# Hall_Effect_Arduino.net
KiCad netlist of a schematic drawn in EAGLE
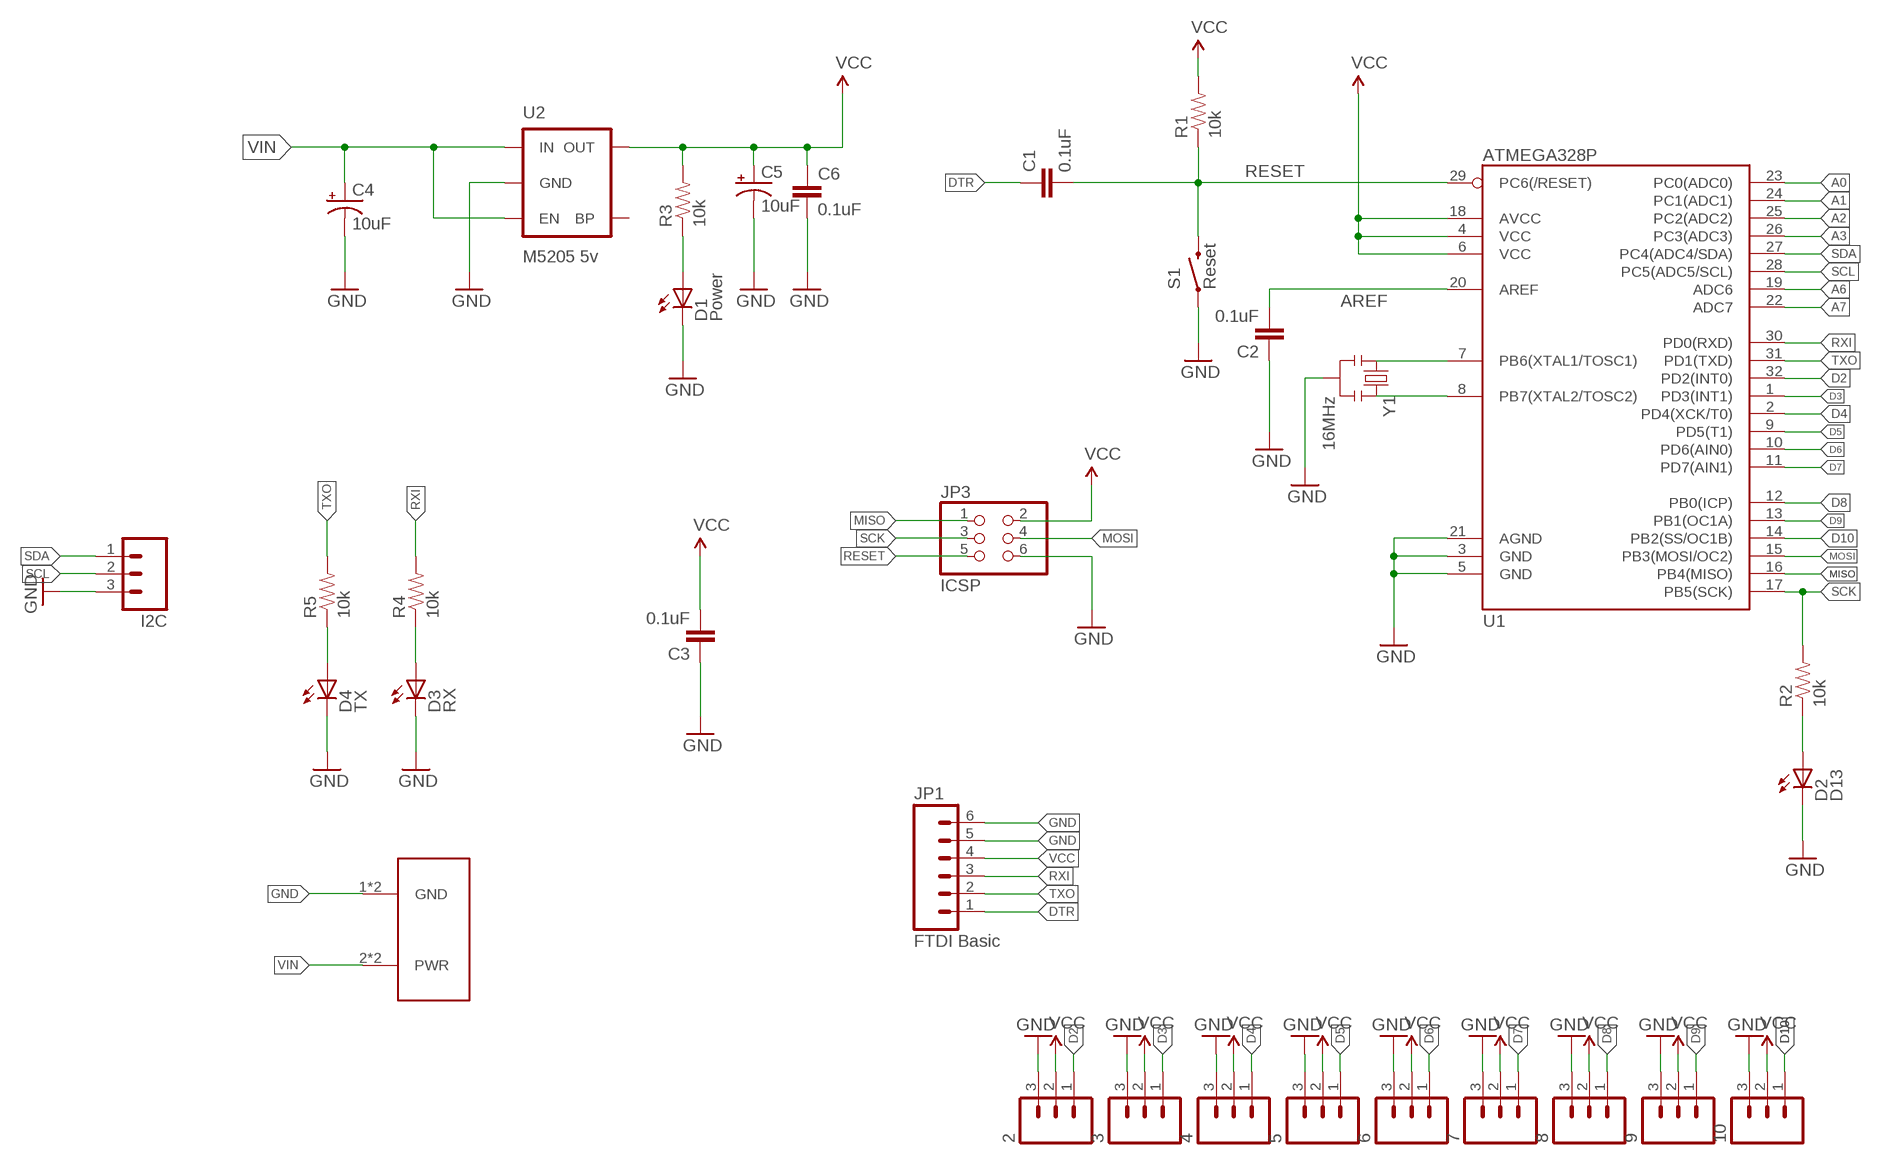
[diagram p0: schematic, sheet 1]

(export (version "E")
  (design (tool "Eeschema 10.0.6"))
  (components
    (comp (ref "2")
      (value "M03PTH")
      (footprint "eagle-import:1X03")
      (libsource (lib "eagle-import") (part "M03PTH"))
    )
    (comp (ref "3")
      (value "M03PTH")
      (footprint "eagle-import:1X03")
      (libsource (lib "eagle-import") (part "M03PTH"))
    )
    (comp (ref "4")
      (value "M03PTH")
      (footprint "eagle-import:1X03")
      (libsource (lib "eagle-import") (part "M03PTH"))
    )
    (comp (ref "5")
      (value "M03PTH")
      (footprint "eagle-import:1X03")
      (libsource (lib "eagle-import") (part "M03PTH"))
    )
    (comp (ref "6")
      (value "M03PTH")
      (footprint "eagle-import:1X03")
      (libsource (lib "eagle-import") (part "M03PTH"))
    )
    (comp (ref "7")
      (value "M03PTH")
      (footprint "eagle-import:1X03")
      (libsource (lib "eagle-import") (part "M03PTH"))
    )
    (comp (ref "8")
      (value "M03PTH")
      (footprint "eagle-import:1X03")
      (libsource (lib "eagle-import") (part "M03PTH"))
    )
    (comp (ref "9")
      (value "M03PTH")
      (footprint "eagle-import:1X03")
      (libsource (lib "eagle-import") (part "M03PTH"))
    )
    (comp (ref "10")
      (value "M03PTH")
      (footprint "eagle-import:1X03")
      (libsource (lib "eagle-import") (part "M03PTH"))
    )
    (comp (ref "C1")
      (value "0.1uF")
      (footprint "eagle-import:0603-CAP")
      (libsource (lib "eagle-import") (part "CAP0603-CAP"))
    )
    (comp (ref "C2")
      (value "0.1uF")
      (footprint "eagle-import:0603-CAP")
      (libsource (lib "eagle-import") (part "CAP0603-CAP"))
    )
    (comp (ref "C3")
      (value "0.1uF")
      (footprint "eagle-import:0603-CAP")
      (libsource (lib "eagle-import") (part "CAP0603-CAP"))
    )
    (comp (ref "C4")
      (value "10uF")
      (footprint "eagle-import:EIA3216")
      (libsource (lib "eagle-import") (part "CAP_POL1206"))
    )
    (comp (ref "C5")
      (value "10uF")
      (footprint "eagle-import:EIA3216")
      (libsource (lib "eagle-import") (part "CAP_POL1206"))
    )
    (comp (ref "C6")
      (value "0.1uF")
      (footprint "eagle-import:0603-CAP")
      (libsource (lib "eagle-import") (part "CAP0603-CAP"))
    )
    (comp (ref "D1")
      (value "Power")
      (footprint "eagle-import:LED-0603")
      (libsource (lib "eagle-import") (part "LED-RED0603"))
    )
    (comp (ref "D2")
      (value "D13")
      (footprint "eagle-import:LED-0603")
      (libsource (lib "eagle-import") (part "LED-RED0603"))
    )
    (comp (ref "D3")
      (value "RX")
      (footprint "eagle-import:LED-0603")
      (libsource (lib "eagle-import") (part "LED-GREEN0603"))
    )
    (comp (ref "D4")
      (value "TX")
      (footprint "eagle-import:LED-0603")
      (libsource (lib "eagle-import") (part "LED-RED0603"))
    )
    (comp (ref "I2C")
      (value "M03PTH")
      (footprint "eagle-import:1X03")
      (libsource (lib "eagle-import") (part "M03PTH"))
    )
    (comp (ref "JP1")
      (value "FTDI Basic")
      (footprint "eagle-import:1X06")
      (libsource (lib "eagle-import") (part "M06SIP"))
    )
    (comp (ref "JP3")
      (value "ICSP")
      (footprint "eagle-import:2X03")
      (libsource (lib "eagle-import") (part "PINHD-2X3"))
    )
    (comp (ref "R1")
      (value "10k")
      (footprint "eagle-import:0603-RES")
      (libsource (lib "eagle-import") (part "RESISTOR0603-RES"))
    )
    (comp (ref "R2")
      (value "10k")
      (footprint "eagle-import:0603-RES")
      (libsource (lib "eagle-import") (part "RESISTOR0603-RES"))
    )
    (comp (ref "R3")
      (value "10k")
      (footprint "eagle-import:0603-RES")
      (libsource (lib "eagle-import") (part "RESISTOR0603-RES"))
    )
    (comp (ref "R4")
      (value "10k")
      (footprint "eagle-import:0603-RES")
      (libsource (lib "eagle-import") (part "RESISTOR0603-RES"))
    )
    (comp (ref "R5")
      (value "10k")
      (footprint "eagle-import:0603-RES")
      (libsource (lib "eagle-import") (part "RESISTOR0603-RES"))
    )
    (comp (ref "S1")
      (value "Reset")
      (footprint "eagle-import:TACTILE_SWITCH_SMD")
      (libsource (lib "eagle-import") (part "SWITCH-MOMENTARY-2SMD"))
    )
    (comp (ref "U$1")
      (value "LSF-SMT")
      (footprint "eagle-import:LSF-SMT")
      (libsource (lib "eagle-import") (part "LSF-SMT"))
    )
    (comp (ref "U1")
      (value "ATMEGA328P")
      (footprint "eagle-import:TQFP32-08")
      (libsource (lib "eagle-import") (part "ATMEGA328_SMT"))
    )
    (comp (ref "U2")
      (value "M5205 5v")
      (footprint "eagle-import:SOT23-5")
      (libsource (lib "eagle-import") (part "MIC52055V"))
    )
    (comp (ref "Y1")
      (value "16MHz")
      (footprint "eagle-import:RESONATOR-SMD")
      (libsource (lib "eagle-import") (part "RESONATOR16MHZ"))
    )
  )
  (nets
    (net (code "1") (name "/AREF") (class "Default")
      (node (ref "C2") (pin "2") (pinfunction "2_2") (pintype "passive"))
      (node (ref "U1") (pin "20") (pinfunction "AREF_20") (pintype "bidirectional"))
    )
    (net (code "2") (name "A0") (class "Default")
      (node (ref "U1") (pin "23") (pinfunction "PC0(ADC0)_23") (pintype "bidirectional"))
    )
    (net (code "3") (name "A1") (class "Default")
      (node (ref "U1") (pin "24") (pinfunction "PC1(ADC1)_24") (pintype "bidirectional"))
    )
    (net (code "4") (name "A2") (class "Default")
      (node (ref "U1") (pin "25") (pinfunction "PC2(ADC2)_25") (pintype "bidirectional"))
    )
    (net (code "5") (name "A3") (class "Default")
      (node (ref "U1") (pin "26") (pinfunction "PC3(ADC3)_26") (pintype "bidirectional"))
    )
    (net (code "6") (name "A6") (class "Default")
      (node (ref "U1") (pin "19") (pinfunction "ADC6_19") (pintype "bidirectional"))
    )
    (net (code "7") (name "A7") (class "Default")
      (node (ref "U1") (pin "22") (pinfunction "ADC7_22") (pintype "bidirectional"))
    )
    (net (code "8") (name "D2") (class "Default")
      (node (ref "2") (pin "1") (pinfunction "1_1") (pintype "passive"))
      (node (ref "U1") (pin "32") (pinfunction "PD2(INT0)_32") (pintype "bidirectional"))
    )
    (net (code "9") (name "D3") (class "Default")
      (node (ref "3") (pin "1") (pinfunction "1_1") (pintype "passive"))
      (node (ref "U1") (pin "1") (pinfunction "PD3(INT1)_1") (pintype "bidirectional"))
    )
    (net (code "10") (name "D4") (class "Default")
      (node (ref "4") (pin "1") (pinfunction "1_1") (pintype "passive"))
      (node (ref "U1") (pin "2") (pinfunction "PD4(XCK/T0)_2") (pintype "bidirectional"))
    )
    (net (code "11") (name "D5") (class "Default")
      (node (ref "5") (pin "1") (pinfunction "1_1") (pintype "passive"))
      (node (ref "U1") (pin "9") (pinfunction "PD5(T1)_9") (pintype "bidirectional"))
    )
    (net (code "12") (name "D6") (class "Default")
      (node (ref "6") (pin "1") (pinfunction "1_1") (pintype "passive"))
      (node (ref "U1") (pin "10") (pinfunction "PD6(AIN0)_10") (pintype "bidirectional"))
    )
    (net (code "13") (name "D7") (class "Default")
      (node (ref "7") (pin "1") (pinfunction "1_1") (pintype "passive"))
      (node (ref "U1") (pin "11") (pinfunction "PD7(AIN1)_11") (pintype "bidirectional"))
    )
    (net (code "14") (name "D8") (class "Default")
      (node (ref "8") (pin "1") (pinfunction "1_1") (pintype "passive"))
      (node (ref "U1") (pin "12") (pinfunction "PB0(ICP)_12") (pintype "bidirectional"))
    )
    (net (code "15") (name "D9") (class "Default")
      (node (ref "9") (pin "1") (pinfunction "1_1") (pintype "passive"))
      (node (ref "U1") (pin "13") (pinfunction "PB1(OC1A)_13") (pintype "bidirectional"))
    )
    (net (code "16") (name "D10") (class "Default")
      (node (ref "10") (pin "1") (pinfunction "1_1") (pintype "passive"))
      (node (ref "U1") (pin "14") (pinfunction "PB2(SS/OC1B)_14") (pintype "bidirectional"))
    )
    (net (code "17") (name "DTR") (class "Default")
      (node (ref "C1") (pin "1") (pinfunction "1_1") (pintype "passive"))
      (node (ref "JP1") (pin "1") (pinfunction "1_1") (pintype "passive"))
    )
    (net (code "18") (name "GND") (class "Default")
      (node (ref "10") (pin "3") (pinfunction "3_3") (pintype "passive"))
      (node (ref "2") (pin "3") (pinfunction "3_3") (pintype "passive"))
      (node (ref "3") (pin "3") (pinfunction "3_3") (pintype "passive"))
      (node (ref "4") (pin "3") (pinfunction "3_3") (pintype "passive"))
      (node (ref "5") (pin "3") (pinfunction "3_3") (pintype "passive"))
      (node (ref "6") (pin "3") (pinfunction "3_3") (pintype "passive"))
      (node (ref "7") (pin "3") (pinfunction "3_3") (pintype "passive"))
      (node (ref "8") (pin "3") (pinfunction "3_3") (pintype "passive"))
      (node (ref "9") (pin "3") (pinfunction "3_3") (pintype "passive"))
      (node (ref "C2") (pin "1") (pinfunction "1_1") (pintype "passive"))
      (node (ref "C3") (pin "1") (pinfunction "1_1") (pintype "passive"))
      (node (ref "C4") (pin "C") (pinfunction "-_C") (pintype "passive"))
      (node (ref "C5") (pin "C") (pinfunction "-_C") (pintype "passive"))
      (node (ref "C6") (pin "2") (pinfunction "2_2") (pintype "passive"))
      (node (ref "D1") (pin "C") (pinfunction "C_C") (pintype "passive"))
      (node (ref "D2") (pin "C") (pinfunction "C_C") (pintype "passive"))
      (node (ref "D3") (pin "C") (pinfunction "C_C") (pintype "passive"))
      (node (ref "D4") (pin "C") (pinfunction "C_C") (pintype "passive"))
      (node (ref "I2C") (pin "3") (pinfunction "3_3") (pintype "passive"))
      (node (ref "JP1") (pin "5") (pinfunction "5_5") (pintype "passive"))
      (node (ref "JP1") (pin "6") (pinfunction "6_6") (pintype "passive"))
      (node (ref "JP3") (pin "6") (pinfunction "6_6") (pintype "passive"))
      (node (ref "S1") (pin "1") (pinfunction "1_1") (pintype "passive"))
      (node (ref "U$1") (pin "1") (pinfunction "GND_1") (pintype "bidirectional"))
      (node (ref "U$1") (pin "1-2") (pinfunction "GND_1-2") (pintype "bidirectional"))
      (node (ref "U1") (pin "21") (pinfunction "AGND_21") (pintype "bidirectional"))
      (node (ref "U1") (pin "3") (pinfunction "GND_3") (pintype "bidirectional"))
      (node (ref "U1") (pin "5") (pinfunction "GND_5") (pintype "bidirectional"))
      (node (ref "U2") (pin "2") (pinfunction "GND_2") (pintype "input"))
      (node (ref "Y1") (pin "2") (pinfunction "2_2") (pintype "passive"))
    )
    (net (code "19") (name "MISO") (class "Default")
      (node (ref "JP3") (pin "1") (pinfunction "1_1") (pintype "passive"))
      (node (ref "U1") (pin "16") (pinfunction "PB4(MISO)_16") (pintype "bidirectional"))
    )
    (net (code "20") (name "MOSI") (class "Default")
      (node (ref "JP3") (pin "4") (pinfunction "4_4") (pintype "passive"))
      (node (ref "U1") (pin "15") (pinfunction "PB3(MOSI/OC2)_15") (pintype "bidirectional"))
    )
    (net (code "21") (name "Net-(D1-PadA)") (class "Default")
      (node (ref "D1") (pin "A") (pinfunction "A_A") (pintype "passive"))
      (node (ref "R3") (pin "1") (pinfunction "1_1") (pintype "passive"))
    )
    (net (code "22") (name "Net-(D2-PadA)") (class "Default")
      (node (ref "D2") (pin "A") (pinfunction "A_A") (pintype "passive"))
      (node (ref "R2") (pin "1") (pinfunction "1_1") (pintype "passive"))
    )
    (net (code "23") (name "Net-(D3-PadA)") (class "Default")
      (node (ref "D3") (pin "A") (pinfunction "A_A") (pintype "passive"))
      (node (ref "R4") (pin "1") (pinfunction "1_1") (pintype "passive"))
    )
    (net (code "24") (name "Net-(D4-PadA)") (class "Default")
      (node (ref "D4") (pin "A") (pinfunction "A_A") (pintype "passive"))
      (node (ref "R5") (pin "1") (pinfunction "1_1") (pintype "passive"))
    )
    (net (code "25") (name "Net-(U1-PB6(XTAL1{slash}TOSC1))") (class "Default")
      (node (ref "U1") (pin "7") (pinfunction "PB6(XTAL1/TOSC1)_7") (pintype "bidirectional"))
      (node (ref "Y1") (pin "1") (pinfunction "1_1") (pintype "passive"))
    )
    (net (code "26") (name "Net-(U1-PB7(XTAL2{slash}TOSC2))") (class "Default")
      (node (ref "U1") (pin "8") (pinfunction "PB7(XTAL2/TOSC2)_8") (pintype "bidirectional"))
      (node (ref "Y1") (pin "3") (pinfunction "3_3") (pintype "passive"))
    )
    (net (code "27") (name "RESET") (class "Default")
      (node (ref "C1") (pin "2") (pinfunction "2_2") (pintype "passive"))
      (node (ref "JP3") (pin "5") (pinfunction "5_5") (pintype "passive"))
      (node (ref "R1") (pin "1") (pinfunction "1_1") (pintype "passive"))
      (node (ref "S1") (pin "3") (pinfunction "2_3") (pintype "passive"))
      (node (ref "U1") (pin "29") (pinfunction "PC6(/RESET)_29") (pintype "bidirectional"))
    )
    (net (code "28") (name "RXI") (class "Default")
      (node (ref "JP1") (pin "3") (pinfunction "3_3") (pintype "passive"))
      (node (ref "R4") (pin "2") (pinfunction "2_2") (pintype "passive"))
      (node (ref "U1") (pin "30") (pinfunction "PD0(RXD)_30") (pintype "bidirectional"))
    )
    (net (code "29") (name "SCK") (class "Default")
      (node (ref "JP3") (pin "3") (pinfunction "3_3") (pintype "passive"))
      (node (ref "R2") (pin "2") (pinfunction "2_2") (pintype "passive"))
      (node (ref "U1") (pin "17") (pinfunction "PB5(SCK)_17") (pintype "bidirectional"))
    )
    (net (code "30") (name "SCL") (class "Default")
      (node (ref "I2C") (pin "2") (pinfunction "2_2") (pintype "passive"))
      (node (ref "U1") (pin "28") (pinfunction "PC5(ADC5/SCL)_28") (pintype "bidirectional"))
    )
    (net (code "31") (name "SDA") (class "Default")
      (node (ref "I2C") (pin "1") (pinfunction "1_1") (pintype "passive"))
      (node (ref "U1") (pin "27") (pinfunction "PC4(ADC4/SDA)_27") (pintype "bidirectional"))
    )
    (net (code "32") (name "TXO") (class "Default")
      (node (ref "JP1") (pin "2") (pinfunction "2_2") (pintype "passive"))
      (node (ref "R5") (pin "2") (pinfunction "2_2") (pintype "passive"))
      (node (ref "U1") (pin "31") (pinfunction "PD1(TXD)_31") (pintype "bidirectional"))
    )
    (net (code "33") (name "VCC") (class "Default")
      (node (ref "10") (pin "2") (pinfunction "2_2") (pintype "passive"))
      (node (ref "2") (pin "2") (pinfunction "2_2") (pintype "passive"))
      (node (ref "3") (pin "2") (pinfunction "2_2") (pintype "passive"))
      (node (ref "4") (pin "2") (pinfunction "2_2") (pintype "passive"))
      (node (ref "5") (pin "2") (pinfunction "2_2") (pintype "passive"))
      (node (ref "6") (pin "2") (pinfunction "2_2") (pintype "passive"))
      (node (ref "7") (pin "2") (pinfunction "2_2") (pintype "passive"))
      (node (ref "8") (pin "2") (pinfunction "2_2") (pintype "passive"))
      (node (ref "9") (pin "2") (pinfunction "2_2") (pintype "passive"))
      (node (ref "C3") (pin "2") (pinfunction "2_2") (pintype "passive"))
      (node (ref "C5") (pin "A") (pinfunction "+_A") (pintype "passive"))
      (node (ref "C6") (pin "1") (pinfunction "1_1") (pintype "passive"))
      (node (ref "JP1") (pin "4") (pinfunction "4_4") (pintype "passive"))
      (node (ref "JP3") (pin "2") (pinfunction "2_2") (pintype "passive"))
      (node (ref "R1") (pin "2") (pinfunction "2_2") (pintype "passive"))
      (node (ref "R3") (pin "2") (pinfunction "2_2") (pintype "passive"))
      (node (ref "U1") (pin "18") (pinfunction "AVCC_18") (pintype "bidirectional"))
      (node (ref "U1") (pin "4") (pinfunction "VCC_4") (pintype "bidirectional"))
      (node (ref "U1") (pin "6") (pinfunction "VCC_6") (pintype "bidirectional"))
      (node (ref "U2") (pin "5") (pinfunction "OUT_5") (pintype "passive"))
    )
    (net (code "34") (name "VIN") (class "Default")
      (node (ref "C4") (pin "A") (pinfunction "+_A") (pintype "passive"))
      (node (ref "U$1") (pin "2") (pinfunction "PWR_2") (pintype "bidirectional"))
      (node (ref "U$1") (pin "2-2") (pinfunction "PWR_2-2") (pintype "bidirectional"))
      (node (ref "U2") (pin "1") (pinfunction "IN_1") (pintype "input"))
      (node (ref "U2") (pin "3") (pinfunction "EN_3") (pintype "input"))
    )
    (net (code "35") (name "unconnected-(U2-BP-Pad4)") (class "Default")
      (node (ref "U2") (pin "4") (pinfunction "BP_4") (pintype "input"))
    )
  )
)
